# mixer-tx.net
KiCad netlist of a schematic drawn in Altium Designer
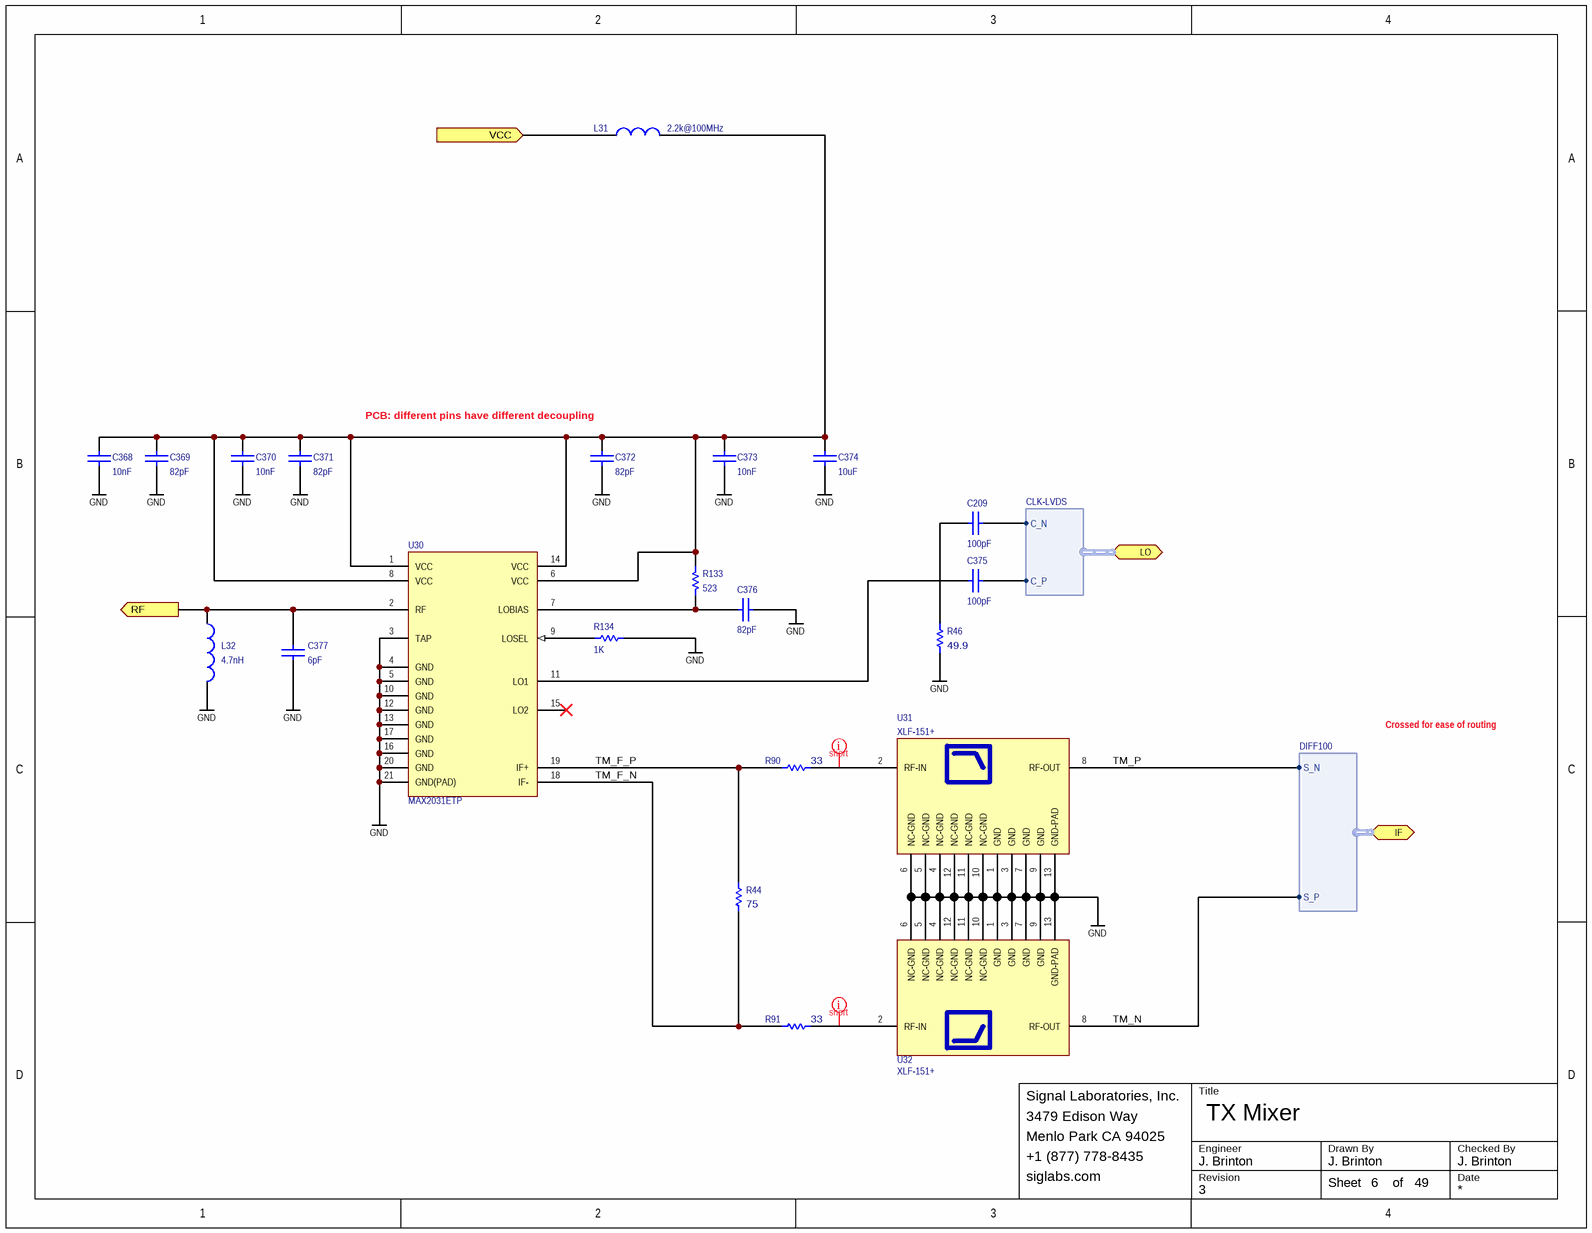
[diagram p0: mixer-tx.SchDoc]

(export (version "E")
  (design (tool "Eeschema 10.0.6"))
  (components
    (comp (ref "C209")
      (value "100pF")
      (footprint "CAPC100X50X55L25N")
      (description "Ceramic Capacitor 100pF ±1% 25V NP0 0402")
      (fields (field (name "VOLTAGE") "25V") (field (name "MANUFACTURER") "Kemet"))
      (libsource (lib "generic") (part "CAP 0603"))
    )
    (comp (ref "C368")
      (value "10nF")
      (footprint "CAPC100X50X55L25N")
      (description "Ceramic Capacitor 10nF ±10% 50V X7R 0402")
      (fields (field (name "VOLTAGE") "50V") (field (name "MANUFACTURER") "Murata"))
      (libsource (lib "Graviton") (part "CAP 0402"))
    )
    (comp (ref "C369")
      (value "82pF")
      (footprint "CAPC100X50X55L25N")
      (description "Ceramic Capacitor 82pF ±5% 25V NP0 0402")
      (fields (field (name "MANUFACTURER") "Vishay") (field (name "VOLTAGE") "25V"))
      (libsource (lib "generic") (part "CAP"))
    )
    (comp (ref "C370")
      (value "10nF")
      (footprint "CAPC100X50X55L25N")
      (description "Ceramic Capacitor 10nF ±10% 50V X7R 0402")
      (fields (field (name "VOLTAGE") "50V") (field (name "MANUFACTURER") "Murata"))
      (libsource (lib "Graviton") (part "CAP 0402"))
    )
    (comp (ref "C371")
      (value "82pF")
      (footprint "CAPC100X50X55L25N")
      (description "Ceramic Capacitor 82pF ±5% 25V NP0 0402")
      (fields (field (name "VOLTAGE") "25V") (field (name "MANUFACTURER") "Vishay"))
      (libsource (lib "generic") (part "CAP"))
    )
    (comp (ref "C372")
      (value "82pF")
      (footprint "CAPC100X50X55L25N")
      (description "Ceramic Capacitor 82pF ±5% 25V NP0 0402")
      (fields (field (name "MANUFACTURER") "Vishay") (field (name "VOLTAGE") "25V"))
      (libsource (lib "generic") (part "CAP"))
    )
    (comp (ref "C373")
      (value "10nF")
      (footprint "CAPC100X50X55L25N")
      (description "Ceramic Capacitor 10nF ±10% 50V X7R 0402")
      (fields (field (name "VOLTAGE") "50V") (field (name "MANUFACTURER") "Murata"))
      (libsource (lib "Graviton") (part "CAP 0402"))
    )
    (comp (ref "C374")
      (value "10uF")
      (footprint "CAPC160X80X90L20N")
      (description "Ceramic Capacitor 10uF ±20% 25V X5R 0603")
      (fields (field (name "MANUFACTURER") "Murata") (field (name "VOLTAGE") "25V"))
      (libsource (lib "generic") (part "CAP 0603"))
    )
    (comp (ref "C375")
      (value "100pF")
      (footprint "CAPC100X50X55L25N")
      (description "Ceramic Capacitor 100pF ±1% 25V NP0 0402")
      (fields (field (name "VOLTAGE") "25V") (field (name "MANUFACTURER") "Kemet"))
      (libsource (lib "generic") (part "CAP 0603"))
    )
    (comp (ref "C376")
      (value "82pF")
      (footprint "CAPC100X50X55L25N")
      (description "Ceramic Capacitor 82pF ±5% 25V NP0 0402")
      (fields (field (name "VOLTAGE") "25V") (field (name "MANUFACTURER") "Vishay"))
      (libsource (lib "generic") (part "CAP"))
    )
    (comp (ref "C377")
      (value "6pF")
      (footprint "CAPC100X50X55L25N")
      (description "Ceramic Capacitor 6pF ±0.25pF 50V NP0 RF 0402")
      (fields (field (name "VOLTAGE") "50V") (field (name "MANUFACTURER") "Murata"))
      (libsource (lib "generic") (part "CAP 0402"))
    )
    (comp (ref "L31")
      (value "2.2k@100MHz")
      (footprint "INDC1005X55N")
      (description "Ferrite Bead 2.2k@100MHz 150mA 0402")
      (fields (field (name "MANUFACTURER") "TDK") (field (name "Comment") "MMZ1005A222ET000"))
      (libsource (lib "*") (part "INDUCTANCE1"))
    )
    (comp (ref "L32")
      (value "4.7nH")
      (footprint "generic:0603")
      (description "Inductor 4.7nH ±0.3nH 0603")
      (fields (field (name "MANUFACTURER") "Murata") (field (name "TOLERANCE") "±0.3nH"))
      (libsource (lib "Graviton") (part "IND 0603"))
    )
    (comp (ref "R44")
      (value "75")
      (footprint "generic:RESC1608X55N")
      (description "Thin Film Resistor 75 Ohm ±0.1% 0603")
      (fields (field (name "MANUFACTURER") "Vishay") (field (name "TOLERANCE") "±0.1%"))
      (libsource (lib "Graviton") (part "RES 0603"))
    )
    (comp (ref "R46")
      (value "49.9")
      (footprint "generic:RESC1608X55N")
      (description "Thin Film Resistor 49.9 Ohm ±0.5% 0603")
      (fields (field (name "MANUFACTURER") "Vishay") (field (name "TOLERANCE") "±0.5%"))
      (libsource (lib "Graviton") (part "RES 0603"))
    )
    (comp (ref "R90")
      (value "33")
      (footprint "generic:RESC1005X40N")
      (description "Thin Film Resistor 33 Ohm ±1% 0402")
      (fields (field (name "MANUFACTURER") "Vishay") (field (name "TOLERANCE") "±1%"))
      (libsource (lib "Graviton") (part "RES 0603"))
    )
    (comp (ref "R91")
      (value "33")
      (footprint "generic:RESC1005X40N")
      (description "Thin Film Resistor 33 Ohm ±1% 0402")
      (fields (field (name "MANUFACTURER") "Vishay") (field (name "TOLERANCE") "±1%"))
      (libsource (lib "Graviton") (part "RES 0603"))
    )
    (comp (ref "R133")
      (value "523")
      (footprint "RESC1005X40N")
      (description "Thin Film Resistor 523 ±0.1% 0402")
      (fields (field (name "MANUFACTURER") "Panasonic") (field (name "TOLERANCE") "±0.1%"))
      (libsource (lib "Graviton") (part "RES 0402"))
    )
    (comp (ref "R134")
      (value "1K")
      (footprint "RESC1005X40N")
      (description "Thick Film Resistor 1k ±1% 0402")
      (fields (field (name "MANUFACTURER") "Yageo") (field (name "TOLERANCE") "±1%"))
      (libsource (lib "Graviton") (part "RES 0402"))
    )
    (comp (ref "U30")
      (value "MAX2031ETP")
      (footprint "QFN21P65_500X500X80L55X30T320N")
      (description "Upconversion/Downconversion Mixer")
      (fields (field (name "MANUFACTURER") "Maxim"))
      (libsource (lib "maxim") (part "MAX2031ETP"))
    )
    (comp (ref "U31")
      (value "XLF-151+")
      (footprint "QFN-XLF-12")
      (description "Reflectionless Low-Pass Filter, DC-150Mhz")
      (fields (field (name "MANUFACTURER") "Mini-Circuits"))
      (libsource (lib "") (part "XLF-151+_1"))
    )
    (comp (ref "U32")
      (value "XLF-151+")
      (footprint "QFN-XLF-12")
      (description "Reflectionless Low-Pass Filter, DC-150Mhz")
      (fields (field (name "MANUFACTURER") "Mini-Circuits"))
      (libsource (lib "Mini-Circuits") (part "XLF-151+"))
    )
  )
  (nets
    (net (code "3") (name "/C_N") (class "Default")
      (node (ref "C209") (pin "2") (pinfunction "2_2") (pintype "passive"))
    )
    (net (code "4") (name "/C_P") (class "Default")
      (node (ref "C375") (pin "2") (pinfunction "2_2") (pintype "passive"))
    )
    (net (code "5") (name "/RF") (class "Default")
      (node (ref "C377") (pin "2") (pinfunction "2_2") (pintype "passive"))
      (node (ref "L32") (pin "2") (pinfunction "2_2") (pintype "passive"))
      (node (ref "U30") (pin "2") (pinfunction "RF_2") (pintype "passive"))
    )
    (net (code "6") (name "/TM_F_N") (class "Default")
      (node (ref "R44") (pin "1") (pinfunction "1_1") (pintype "passive"))
      (node (ref "R91") (pin "2") (pinfunction "2_2") (pintype "passive"))
      (node (ref "U30") (pin "18") (pinfunction "IF-_18") (pintype "passive"))
    )
    (net (code "7") (name "/TM_F_P") (class "Default")
      (node (ref "R44") (pin "2") (pinfunction "2_2") (pintype "passive"))
      (node (ref "R90") (pin "2") (pinfunction "2_2") (pintype "passive"))
      (node (ref "U30") (pin "19") (pinfunction "IF+_19") (pintype "passive"))
    )
    (net (code "8") (name "/TM_N") (class "Default")
      (node (ref "U32") (pin "8") (pinfunction "RF-OUT_8") (pintype "passive"))
    )
    (net (code "9") (name "/TM_P") (class "Default")
      (node (ref "U31") (pin "8") (pinfunction "RF-OUT_8") (pintype "passive"))
    )
    (net (code "10") (name "/VCC") (class "Default")
      (node (ref "L31") (pin "1") (pinfunction "1_1") (pintype "passive"))
    )
    (net (code "13") (name "GND") (class "Default")
      (node (ref "C368") (pin "1") (pinfunction "1_1") (pintype "passive"))
      (node (ref "C369") (pin "1") (pinfunction "1_1") (pintype "passive"))
      (node (ref "C370") (pin "1") (pinfunction "1_1") (pintype "passive"))
      (node (ref "C371") (pin "1") (pinfunction "1_1") (pintype "passive"))
      (node (ref "C372") (pin "1") (pinfunction "1_1") (pintype "passive"))
      (node (ref "C373") (pin "1") (pinfunction "1_1") (pintype "passive"))
      (node (ref "C374") (pin "1") (pinfunction "1_1") (pintype "passive"))
      (node (ref "C376") (pin "2") (pinfunction "2_2") (pintype "passive"))
      (node (ref "C377") (pin "1") (pinfunction "1_1") (pintype "passive"))
      (node (ref "L32") (pin "1") (pinfunction "1_1") (pintype "passive"))
      (node (ref "R134") (pin "2") (pinfunction "2_2") (pintype "passive"))
      (node (ref "R46") (pin "1") (pinfunction "1_1") (pintype "passive"))
      (node (ref "U30") (pin "10") (pinfunction "GND_10") (pintype "power_in"))
      (node (ref "U30") (pin "12") (pinfunction "GND_12") (pintype "power_in"))
      (node (ref "U30") (pin "13") (pinfunction "GND_13") (pintype "power_in"))
      (node (ref "U30") (pin "16") (pinfunction "GND_16") (pintype "power_in"))
      (node (ref "U30") (pin "17") (pinfunction "GND_17") (pintype "power_in"))
      (node (ref "U30") (pin "20") (pinfunction "GND_20") (pintype "power_in"))
      (node (ref "U30") (pin "21") (pinfunction "GND(PAD)_21") (pintype "power_in"))
      (node (ref "U30") (pin "3") (pinfunction "TAP_3") (pintype "passive"))
      (node (ref "U30") (pin "4") (pinfunction "GND_4") (pintype "power_in"))
      (node (ref "U30") (pin "5") (pinfunction "GND_5") (pintype "power_in"))
      (node (ref "U31") (pin "1") (pinfunction "GND_1") (pintype "passive"))
      (node (ref "U31") (pin "10") (pinfunction "NC-GND_10") (pintype "passive"))
      (node (ref "U31") (pin "11") (pinfunction "NC-GND_11") (pintype "passive"))
      (node (ref "U31") (pin "12") (pinfunction "NC-GND_12") (pintype "passive"))
      (node (ref "U31") (pin "13") (pinfunction "GND-PAD_13") (pintype "passive"))
      (node (ref "U31") (pin "3") (pinfunction "GND_3") (pintype "passive"))
      (node (ref "U31") (pin "4") (pinfunction "NC-GND_4") (pintype "passive"))
      (node (ref "U31") (pin "5") (pinfunction "NC-GND_5") (pintype "passive"))
      (node (ref "U31") (pin "6") (pinfunction "NC-GND_6") (pintype "passive"))
      (node (ref "U31") (pin "7") (pinfunction "GND_7") (pintype "passive"))
      (node (ref "U31") (pin "9") (pinfunction "GND_9") (pintype "passive"))
      (node (ref "U32") (pin "1") (pinfunction "GND_1") (pintype "passive"))
      (node (ref "U32") (pin "10") (pinfunction "NC-GND_10") (pintype "passive"))
      (node (ref "U32") (pin "11") (pinfunction "NC-GND_11") (pintype "passive"))
      (node (ref "U32") (pin "12") (pinfunction "NC-GND_12") (pintype "passive"))
      (node (ref "U32") (pin "13") (pinfunction "GND-PAD_13") (pintype "passive"))
      (node (ref "U32") (pin "3") (pinfunction "GND_3") (pintype "passive"))
      (node (ref "U32") (pin "4") (pinfunction "NC-GND_4") (pintype "passive"))
      (node (ref "U32") (pin "5") (pinfunction "NC-GND_5") (pintype "passive"))
      (node (ref "U32") (pin "6") (pinfunction "NC-GND_6") (pintype "passive"))
      (node (ref "U32") (pin "7") (pinfunction "GND_7") (pintype "passive"))
      (node (ref "U32") (pin "9") (pinfunction "GND_9") (pintype "passive"))
    )
    (net (code "14") (name "Net-(C209-Pad1)") (class "Default")
      (node (ref "C209") (pin "1") (pinfunction "1_1") (pintype "passive"))
      (node (ref "R46") (pin "2") (pinfunction "2_2") (pintype "passive"))
    )
    (net (code "15") (name "Net-(C368-Pad2)") (class "Default")
      (node (ref "C368") (pin "2") (pinfunction "2_2") (pintype "passive"))
      (node (ref "C369") (pin "2") (pinfunction "2_2") (pintype "passive"))
      (node (ref "C370") (pin "2") (pinfunction "2_2") (pintype "passive"))
      (node (ref "C371") (pin "2") (pinfunction "2_2") (pintype "passive"))
      (node (ref "C372") (pin "2") (pinfunction "2_2") (pintype "passive"))
      (node (ref "C373") (pin "2") (pinfunction "2_2") (pintype "passive"))
      (node (ref "C374") (pin "2") (pinfunction "2_2") (pintype "passive"))
      (node (ref "L31") (pin "2") (pinfunction "2_2") (pintype "passive"))
      (node (ref "R133") (pin "2") (pinfunction "2_2") (pintype "passive"))
      (node (ref "U30") (pin "1") (pinfunction "VCC_1") (pintype "power_in"))
      (node (ref "U30") (pin "14") (pinfunction "VCC_14") (pintype "power_in"))
      (node (ref "U30") (pin "6") (pinfunction "VCC_6") (pintype "power_in"))
      (node (ref "U30") (pin "8") (pinfunction "VCC_8") (pintype "power_in"))
    )
    (net (code "16") (name "Net-(U30-LO1)") (class "Default")
      (node (ref "C375") (pin "1") (pinfunction "1_1") (pintype "passive"))
      (node (ref "U30") (pin "11") (pinfunction "LO1_11") (pintype "passive"))
    )
    (net (code "17") (name "Net-(U30-LOBIAS)") (class "Default")
      (node (ref "C376") (pin "1") (pinfunction "1_1") (pintype "passive"))
      (node (ref "R133") (pin "1") (pinfunction "1_1") (pintype "passive"))
      (node (ref "U30") (pin "7") (pinfunction "LOBIAS_7") (pintype "passive"))
    )
    (net (code "18") (name "Net-(U30-LOSEL)") (class "Default")
      (node (ref "R134") (pin "1") (pinfunction "1_1") (pintype "passive"))
      (node (ref "U30") (pin "9") (pinfunction "LOSEL_9") (pintype "input"))
    )
    (net (code "19") (name "Net-(U31-RF-IN)") (class "Default")
      (node (ref "R90") (pin "1") (pinfunction "1_1") (pintype "passive"))
      (node (ref "U31") (pin "2") (pinfunction "RF-IN_2") (pintype "passive"))
    )
    (net (code "20") (name "Net-(U32-RF-IN)") (class "Default")
      (node (ref "R91") (pin "1") (pinfunction "1_1") (pintype "passive"))
      (node (ref "U32") (pin "2") (pinfunction "RF-IN_2") (pintype "passive"))
    )
    (net (code "21") (name "unconnected-(U30-LO2-Pad15)") (class "Default")
      (node (ref "U30") (pin "15") (pinfunction "LO2_15") (pintype "passive+no_connect"))
    )
  )
)
